# skema.net
KiCad netlist of a schematic drawn in EAGLE
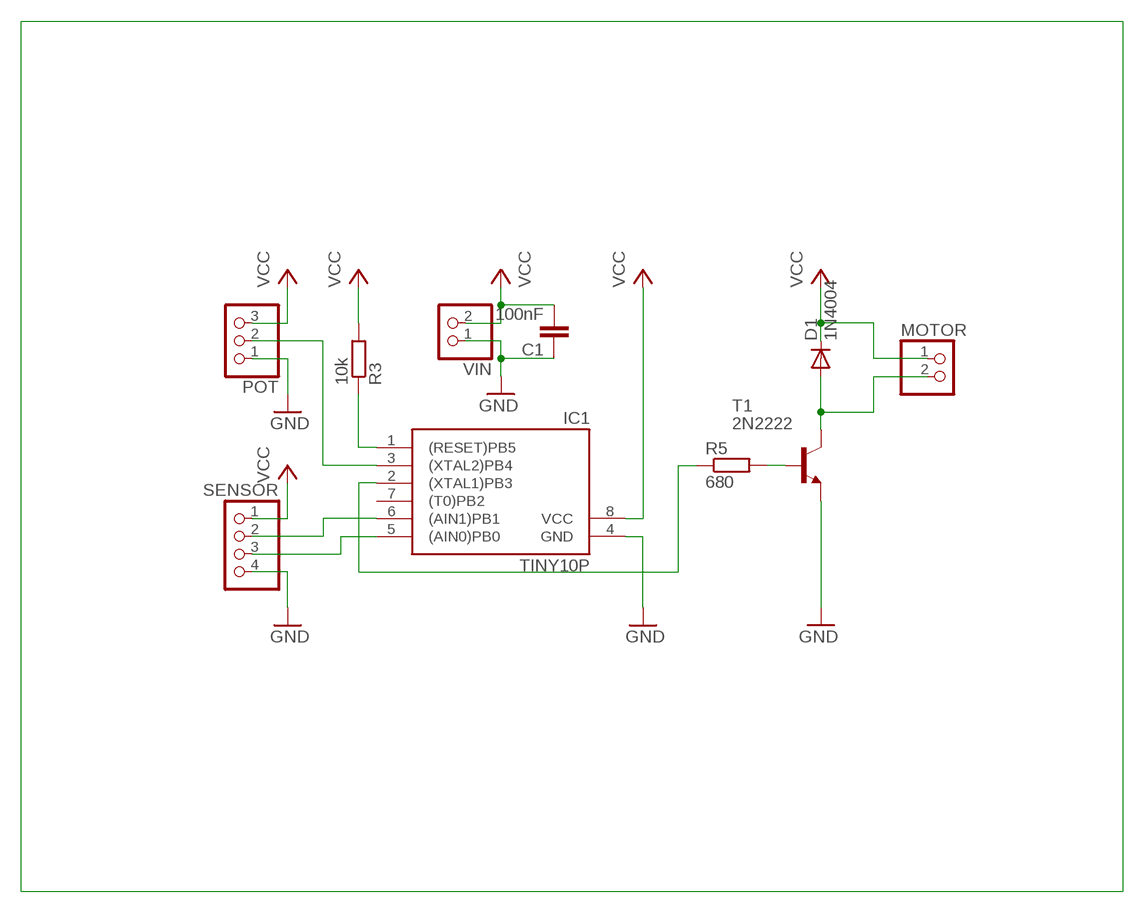
[diagram p0: schematic, sheet 1]

(export (version "E")
  (design (tool "Eeschema 10.0.6"))
  (components
    (comp (ref "C1")
      (value "100nF")
      (footprint "eagle-import:C050-025X075")
      (libsource (lib "eagle-import") (part "C-EU050-025X075"))
    )
    (comp (ref "D1")
      (value "1N4004")
      (footprint "eagle-import:DO41-10")
      (libsource (lib "eagle-import") (part "1N4004"))
    )
    (comp (ref "IC1")
      (value "TINY10P")
      (footprint "eagle-import:DIL08")
      (libsource (lib "eagle-import") (part "TINY10P"))
    )
    (comp (ref "MOTOR")
      (value "PINHD-1X2")
      (footprint "eagle-import:1X02")
      (libsource (lib "eagle-import") (part "PINHD-1X2"))
    )
    (comp (ref "POT")
      (value "PINHD-1X3")
      (footprint "eagle-import:1X03")
      (libsource (lib "eagle-import") (part "PINHD-1X3"))
    )
    (comp (ref "R3")
      (value "10k")
      (footprint "eagle-import:0207_10")
      (libsource (lib "eagle-import") (part "R-EU_0207/10"))
    )
    (comp (ref "R5")
      (value "680")
      (footprint "eagle-import:0207_10")
      (libsource (lib "eagle-import") (part "R-EU_0207/10"))
    )
    (comp (ref "SENSOR")
      (value "PINHD-1X4")
      (footprint "eagle-import:1X04")
      (libsource (lib "eagle-import") (part "PINHD-1X4"))
    )
    (comp (ref "T1")
      (value "2N2222")
      (footprint "eagle-import:TO18")
      (libsource (lib "eagle-import") (part "2N2222"))
    )
    (comp (ref "VIN")
      (value "PINHD-1X2")
      (footprint "eagle-import:1X02")
      (libsource (lib "eagle-import") (part "PINHD-1X2"))
    )
  )
  (nets
    (net (code "1") (name "GND") (class "Default")
      (node (ref "C1") (pin "1") (pinfunction "1_1") (pintype "passive"))
      (node (ref "IC1") (pin "4") (pinfunction "GND_4") (pintype "power_in"))
      (node (ref "POT") (pin "1") (pinfunction "1_1") (pintype "passive"))
      (node (ref "SENSOR") (pin "4") (pinfunction "4_4") (pintype "passive"))
      (node (ref "T1") (pin "1") (pinfunction "E_1") (pintype "passive"))
      (node (ref "VIN") (pin "1") (pinfunction "1_1") (pintype "passive"))
    )
    (net (code "2") (name "Net-(IC1-(AIN0)PB0)") (class "Default")
      (node (ref "IC1") (pin "5") (pinfunction "(AIN0)PB0_5") (pintype "bidirectional"))
      (node (ref "SENSOR") (pin "3") (pinfunction "3_3") (pintype "passive"))
    )
    (net (code "3") (name "Net-(IC1-(AIN1)PB1)") (class "Default")
      (node (ref "IC1") (pin "6") (pinfunction "(AIN1)PB1_6") (pintype "bidirectional"))
      (node (ref "SENSOR") (pin "2") (pinfunction "2_2") (pintype "passive"))
    )
    (net (code "4") (name "Net-(IC1-(RESET)PB5)") (class "Default")
      (node (ref "IC1") (pin "1") (pinfunction "(RESET)PB5_1") (pintype "bidirectional"))
      (node (ref "R3") (pin "1") (pinfunction "1_1") (pintype "passive"))
    )
    (net (code "5") (name "Net-(IC1-(XTAL1)PB3)") (class "Default")
      (node (ref "IC1") (pin "2") (pinfunction "(XTAL1)PB3_2") (pintype "bidirectional"))
      (node (ref "R5") (pin "1") (pinfunction "1_1") (pintype "passive"))
    )
    (net (code "6") (name "Net-(IC1-(XTAL2)PB4)") (class "Default")
      (node (ref "IC1") (pin "3") (pinfunction "(XTAL2)PB4_3") (pintype "bidirectional"))
      (node (ref "POT") (pin "2") (pinfunction "2_2") (pintype "passive"))
    )
    (net (code "7") (name "Net-(T1-B)") (class "Default")
      (node (ref "R5") (pin "2") (pinfunction "2_2") (pintype "passive"))
      (node (ref "T1") (pin "2") (pinfunction "B_2") (pintype "passive"))
    )
    (net (code "8") (name "Net-(T1-C)") (class "Default")
      (node (ref "D1") (pin "A") (pinfunction "A_A") (pintype "passive"))
      (node (ref "MOTOR") (pin "2") (pinfunction "2_2") (pintype "passive"))
      (node (ref "T1") (pin "3") (pinfunction "C_3") (pintype "passive"))
    )
    (net (code "9") (name "VCC") (class "Default")
      (node (ref "C1") (pin "2") (pinfunction "2_2") (pintype "passive"))
      (node (ref "D1") (pin "C") (pinfunction "C_C") (pintype "passive"))
      (node (ref "IC1") (pin "8") (pinfunction "VCC_8") (pintype "power_in"))
      (node (ref "MOTOR") (pin "1") (pinfunction "1_1") (pintype "passive"))
      (node (ref "POT") (pin "3") (pinfunction "3_3") (pintype "passive"))
      (node (ref "R3") (pin "2") (pinfunction "2_2") (pintype "passive"))
      (node (ref "SENSOR") (pin "1") (pinfunction "1_1") (pintype "passive"))
      (node (ref "VIN") (pin "2") (pinfunction "2_2") (pintype "passive"))
    )
    (net (code "10") (name "unconnected-(IC1-(T0)PB2-Pad7)") (class "Default")
      (node (ref "IC1") (pin "7") (pinfunction "(T0)PB2_7") (pintype "bidirectional"))
    )
  )
)
